# ATMEGA.net
KiCad netlist of a schematic drawn in Altium Designer
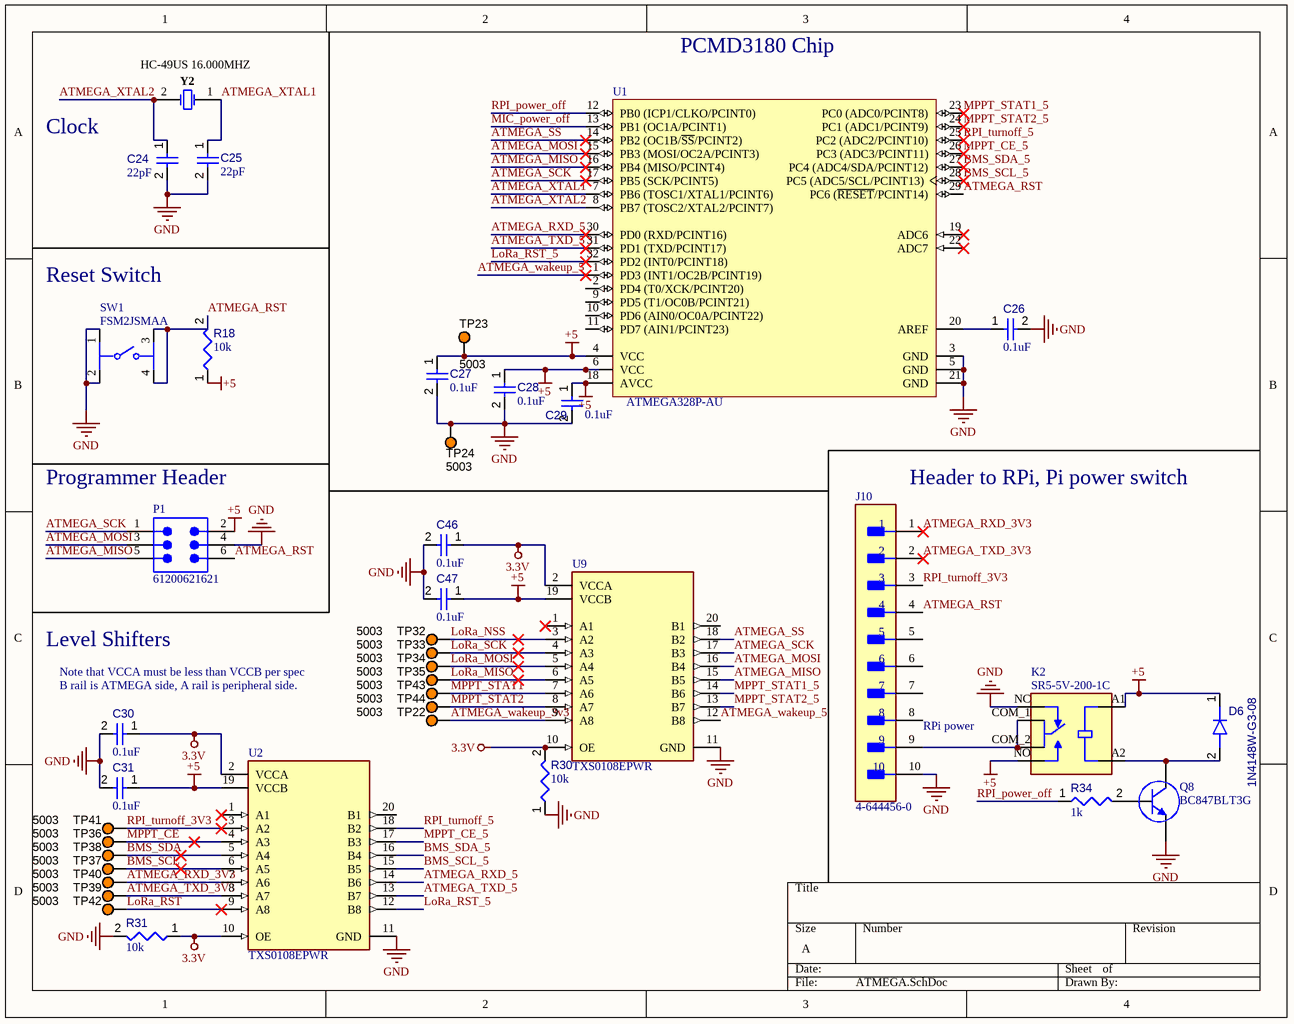
[diagram p0: ATMEGA.SchDoc]

(export (version "E")
  (design (tool "Eeschema 10.0.6"))
  (components
    (comp (ref "C24")
      (value "22pF")
      (footprint "FP-C0603C-CF-IPC_B")
      (fields (field (name "Comment") "C0603C220J5GACTU"))
      (libsource (lib "University of Michigan") (part "CAP-NP-2"))
    )
    (comp (ref "C25")
      (value "22pF")
      (footprint "FP-C0603C-CF-IPC_B")
      (fields (field (name "Comment") "C0603C220J5GACTU"))
      (libsource (lib "University of Michigan") (part "CAP-NP-2"))
    )
    (comp (ref "C26")
      (value "0.1uF")
      (footprint "CAPC1608X90X40NL10T20")
      (description "Chip Capacitor, 100 nF, +/- 10%, 50 V, 0603 (1608 Metric)")
      (fields (field (name "TOLERANCE") "10%") (field (name "Comment") "Capacitor 100 nF +/-10% 50 V 0603"))
      (libsource (lib "University of Michigan") (part "CAP-NP-2"))
    )
    (comp (ref "C27")
      (value "0.1uF")
      (footprint "CAPC1608X90X40NL10T20")
      (description "Chip Capacitor, 100 nF, +/- 10%, 50 V, 0603 (1608 Metric)")
      (fields (field (name "TOLERANCE") "10%") (field (name "Comment") "Capacitor 100 nF +/-10% 50 V 0603"))
      (libsource (lib "University of Michigan") (part "CAP-NP-2"))
    )
    (comp (ref "C28")
      (value "0.1uF")
      (footprint "CAPC1608X90X40NL10T20")
      (description "Chip Capacitor, 100 nF, +/- 10%, 50 V, 0603 (1608 Metric)")
      (fields (field (name "TOLERANCE") "10%") (field (name "Comment") "Capacitor 100 nF +/-10% 50 V 0603"))
      (libsource (lib "University of Michigan") (part "CAP-NP-2"))
    )
    (comp (ref "C29")
      (value "0.1uF")
      (footprint "CAPC1608X90X40NL10T20")
      (description "Chip Capacitor, 100 nF, +/- 10%, 50 V, 0603 (1608 Metric)")
      (fields (field (name "TOLERANCE") "10%") (field (name "Comment") "Capacitor 100 nF +/-10% 50 V 0603"))
      (libsource (lib "University of Michigan") (part "CAP-NP-2"))
    )
    (comp (ref "C30")
      (value "0.1uF")
      (footprint "CAPC1608X90X40NL10T20")
      (description "Chip Capacitor, 100 nF, +/- 10%, 50 V, 0603 (1608 Metric)")
      (fields (field (name "TOLERANCE") "10%") (field (name "Comment") "Capacitor 100 nF +/-10% 50 V 0603"))
      (libsource (lib "University of Michigan") (part "CAP-NP-2"))
    )
    (comp (ref "C31")
      (value "0.1uF")
      (footprint "CAPC1608X90X40NL10T20")
      (description "Chip Capacitor, 100 nF, +/- 10%, 50 V, 0603 (1608 Metric)")
      (fields (field (name "TOLERANCE") "10%") (field (name "Comment") "Capacitor 100 nF +/-10% 50 V 0603"))
      (libsource (lib "University of Michigan") (part "CAP-NP-2"))
    )
    (comp (ref "C46")
      (value "0.1uF")
      (footprint "CAPC1608X90X40NL10T20")
      (description "Chip Capacitor, 100 nF, +/- 10%, 50 V, 0603 (1608 Metric)")
      (fields (field (name "TOLERANCE") "10%") (field (name "Comment") "Capacitor 100 nF +/-10% 50 V 0603"))
      (libsource (lib "University of Michigan") (part "CAP-NP-2"))
    )
    (comp (ref "C47")
      (value "0.1uF")
      (footprint "CAPC1608X90X40NL10T20")
      (description "Chip Capacitor, 100 nF, +/- 10%, 50 V, 0603 (1608 Metric)")
      (fields (field (name "TOLERANCE") "10%") (field (name "Comment") "Capacitor 100 nF +/-10% 50 V 0603"))
      (libsource (lib "University of Michigan") (part "CAP-NP-2"))
    )
    (comp (ref "D6")
      (value "1N4148W-G3-08")
      (footprint "FP-S8-V-3910_01-001-IPC_B")
      (description "Rectifier Diode, 1 Phase, 1 Element, 0.15A, 100V V(RRM), Silicon")
      (libsource (lib "University of Michigan") (part "DIODE-2"))
    )
    (comp (ref "J10")
      (value "4-644456-0")
      (footprint "FP-4-644456-0-MFG")
      (libsource (lib "University of Michigan") (part "aee40dc8b284c03a16094555aa210be"))
    )
    (comp (ref "K2")
      (value "SR5-5V-200-1C")
      (footprint "RELAY_SR5-5V-200-1C")
      (description "15.6 x 10.6 x 11.8 mm, 5 V, 1 A, SPDT (1 Form C), Through Hole, Signal Relay")
      (fields (field (name "MF") "CUI Devices"))
      (libsource (lib "University of Michigan") (part "SR5-5V-200-1C"))
    )
    (comp (ref "P1")
      (value "61200621621")
      (footprint "61200621621")
      (description "Board Connector, 6 Contact(s), 2 Row(s), Male, Straight, Solder Terminal")
      (libsource (lib "University of Michigan") (part "Header_Male_2R_06P"))
    )
    (comp (ref "Q8")
      (value "BC847BLT3G")
      (footprint "ONSC-SOT-23-3-318-08_V")
      (description "Small Signal Bipolar Transistor, 0.1A I(C), 45V V(BR)CEO, 1-Element, NPN, Silicon, TO-236")
      (libsource (lib "University of Michigan") (part "TRANS-NPN-3"))
    )
    (comp (ref "R18")
      (value "10k")
      (footprint "RESC0603(1608)_L")
      (description "Chip Resistor, 120 Ohms, +/-5 %, 0.1 W, -55 to 155 degC, 0603")
      (fields (field (name "POWER") "100mW") (field (name "TOLERANCE") "5%"))
      (libsource (lib "University of Michigan") (part "RES-2"))
    )
    (comp (ref "R30")
      (value "10k")
      (footprint "RESC0603(1608)_L")
      (description "Chip Resistor, 120 Ohms, +/-5 %, 0.1 W, -55 to 155 degC, 0603")
      (fields (field (name "POWER") "100mW") (field (name "TOLERANCE") "5%"))
      (libsource (lib "University of Michigan") (part "RES-2"))
    )
    (comp (ref "R31")
      (value "10k")
      (footprint "RESC0603(1608)_L")
      (description "Chip Resistor, 120 Ohms, +/-5 %, 0.1 W, -55 to 155 degC, 0603")
      (fields (field (name "POWER") "100mW") (field (name "TOLERANCE") "5%"))
      (libsource (lib "University of Michigan") (part "RES-2"))
    )
    (comp (ref "R34")
      (value "1k")
      (footprint "RESC0603(1608)_L")
      (description "Chip Resistor, 120 Ohms, +/-5 %, 0.1 W, -55 to 155 degC, 0603")
      (fields (field (name "POWER") "100mW") (field (name "TOLERANCE") "5%"))
      (libsource (lib "University of Michigan") (part "RES-2"))
    )
    (comp (ref "SW1")
      (value "FSM2JSMAA")
      (footprint "FP-FSM2JSMAA-MFG")
      (libsource (lib "University of Michigan") (part "b8895f3f4cefb76e1819d2863dba89b"))
    )
    (comp (ref "TP22")
      (value "5003")
      (footprint "KSTN-5003")
      (description "Test Point, Orange, Height 4.6 mm, Tail Length 3 mm, 1-Pin THD, RoHS")
      (fields (field (name "MANUFACTURER") "Keystone"))
      (libsource (lib "University of Michigan") (part "TESTPOINT_ORANGE"))
    )
    (comp (ref "TP23")
      (value "5003")
      (footprint "KSTN-5003")
      (description "Test Point, Orange, Height 4.6 mm, Tail Length 3 mm, 1-Pin THD, RoHS")
      (fields (field (name "MANUFACTURER") "Keystone"))
      (libsource (lib "University of Michigan") (part "TESTPOINT_ORANGE"))
    )
    (comp (ref "TP24")
      (value "5003")
      (footprint "KSTN-5003")
      (description "Test Point, Orange, Height 4.6 mm, Tail Length 3 mm, 1-Pin THD, RoHS")
      (fields (field (name "MANUFACTURER") "Keystone"))
      (libsource (lib "University of Michigan") (part "TESTPOINT_ORANGE"))
    )
    (comp (ref "TP32")
      (value "5003")
      (footprint "KSTN-5003")
      (description "Test Point, Orange, Height 4.6 mm, Tail Length 3 mm, 1-Pin THD, RoHS")
      (fields (field (name "MANUFACTURER") "Keystone"))
      (libsource (lib "University of Michigan") (part "TESTPOINT_ORANGE"))
    )
    (comp (ref "TP33")
      (value "5003")
      (footprint "KSTN-5003")
      (description "Test Point, Orange, Height 4.6 mm, Tail Length 3 mm, 1-Pin THD, RoHS")
      (fields (field (name "MANUFACTURER") "Keystone"))
      (libsource (lib "University of Michigan") (part "TESTPOINT_ORANGE"))
    )
    (comp (ref "TP34")
      (value "5003")
      (footprint "KSTN-5003")
      (description "Test Point, Orange, Height 4.6 mm, Tail Length 3 mm, 1-Pin THD, RoHS")
      (fields (field (name "MANUFACTURER") "Keystone"))
      (libsource (lib "University of Michigan") (part "TESTPOINT_ORANGE"))
    )
    (comp (ref "TP35")
      (value "5003")
      (footprint "KSTN-5003")
      (description "Test Point, Orange, Height 4.6 mm, Tail Length 3 mm, 1-Pin THD, RoHS")
      (fields (field (name "MANUFACTURER") "Keystone"))
      (libsource (lib "University of Michigan") (part "TESTPOINT_ORANGE"))
    )
    (comp (ref "TP36")
      (value "5003")
      (footprint "KSTN-5003")
      (description "Test Point, Orange, Height 4.6 mm, Tail Length 3 mm, 1-Pin THD, RoHS")
      (fields (field (name "MANUFACTURER") "Keystone"))
      (libsource (lib "University of Michigan") (part "TESTPOINT_ORANGE"))
    )
    (comp (ref "TP37")
      (value "5003")
      (footprint "KSTN-5003")
      (description "Test Point, Orange, Height 4.6 mm, Tail Length 3 mm, 1-Pin THD, RoHS")
      (fields (field (name "MANUFACTURER") "Keystone"))
      (libsource (lib "University of Michigan") (part "TESTPOINT_ORANGE"))
    )
    (comp (ref "TP38")
      (value "5003")
      (footprint "KSTN-5003")
      (description "Test Point, Orange, Height 4.6 mm, Tail Length 3 mm, 1-Pin THD, RoHS")
      (fields (field (name "MANUFACTURER") "Keystone"))
      (libsource (lib "University of Michigan") (part "TESTPOINT_ORANGE"))
    )
    (comp (ref "TP39")
      (value "5003")
      (footprint "KSTN-5003")
      (description "Test Point, Orange, Height 4.6 mm, Tail Length 3 mm, 1-Pin THD, RoHS")
      (fields (field (name "MANUFACTURER") "Keystone"))
      (libsource (lib "University of Michigan") (part "TESTPOINT_ORANGE"))
    )
    (comp (ref "TP40")
      (value "5003")
      (footprint "KSTN-5003")
      (description "Test Point, Orange, Height 4.6 mm, Tail Length 3 mm, 1-Pin THD, RoHS")
      (fields (field (name "MANUFACTURER") "Keystone"))
      (libsource (lib "University of Michigan") (part "TESTPOINT_ORANGE"))
    )
    (comp (ref "TP41")
      (value "5003")
      (footprint "KSTN-5003")
      (description "Test Point, Orange, Height 4.6 mm, Tail Length 3 mm, 1-Pin THD, RoHS")
      (fields (field (name "MANUFACTURER") "Keystone"))
      (libsource (lib "University of Michigan") (part "TESTPOINT_ORANGE"))
    )
    (comp (ref "TP42")
      (value "5003")
      (footprint "KSTN-5003")
      (description "Test Point, Orange, Height 4.6 mm, Tail Length 3 mm, 1-Pin THD, RoHS")
      (fields (field (name "MANUFACTURER") "Keystone"))
      (libsource (lib "University of Michigan") (part "TESTPOINT_ORANGE"))
    )
    (comp (ref "TP43")
      (value "5003")
      (footprint "KSTN-5003")
      (description "Test Point, Orange, Height 4.6 mm, Tail Length 3 mm, 1-Pin THD, RoHS")
      (fields (field (name "MANUFACTURER") "Keystone"))
      (libsource (lib "University of Michigan") (part "TESTPOINT_ORANGE"))
    )
    (comp (ref "TP44")
      (value "5003")
      (footprint "KSTN-5003")
      (description "Test Point, Orange, Height 4.6 mm, Tail Length 3 mm, 1-Pin THD, RoHS")
      (fields (field (name "MANUFACTURER") "Keystone"))
      (libsource (lib "University of Michigan") (part "TESTPOINT_ORANGE"))
    )
    (comp (ref "U1")
      (value "ATMEGA328P-AU")
      (footprint "ATML-32A_M")
      (fields (field (name "MANUFACTURER") "Atmel"))
      (libsource (lib "University of Michigan") (part "ATML-ATMEGAX8A-32A"))
    )
    (comp (ref "U2")
      (value "TXS0108EPWR")
      (footprint "FP-PW0020A-IPC_A")
      (description "Interface Circuit, PDSO20")
      (libsource (lib "University of Michigan") (part "86128ddf5852d4e934b2dd0188c13f1"))
    )
    (comp (ref "U9")
      (value "TXS0108EPWR")
      (footprint "FP-PW0020A-IPC_A")
      (description "Interface Circuit, PDSO20")
      (libsource (lib "University of Michigan") (part "86128ddf5852d4e934b2dd0188c13f1"))
    )
    (comp (ref "Y2")
      (value "HC-49US 16.000MHZ")
      (footprint "JPY-HC-49US")
      (description "Crystal, 16 MHz, +/- 30 ppm, 18 pF, -20 to 70 degC, 2-Pin THD")
      (fields (field (name "MANUFACTURER") "Jing peng yuan"))
      (libsource (lib "University of Michigan") (part "XTAL-1-2-2"))
    )
  )
  (nets
    (net (code "1") (name "+5") (class "Default")
      (node (ref "C27") (pin "1") (pinfunction "1_1") (pintype "passive"))
      (node (ref "C28") (pin "1") (pinfunction "1_1") (pintype "passive"))
      (node (ref "C29") (pin "1") (pinfunction "1_1") (pintype "passive"))
      (node (ref "C31") (pin "1") (pinfunction "1_1") (pintype "passive"))
      (node (ref "C47") (pin "1") (pinfunction "1_1") (pintype "passive"))
      (node (ref "D6") (pin "1") (pinfunction "K_1") (pintype "passive"))
      (node (ref "K2") (pin "A1") (pinfunction "COIL1_A1") (pintype "passive"))
      (node (ref "K2") (pin "NO") (pinfunction "NO_NO") (pintype "passive"))
      (node (ref "P1") (pin "2") (pinfunction "2_2") (pintype "passive"))
      (node (ref "R18") (pin "1") (pinfunction "1_1") (pintype "passive"))
      (node (ref "TP23") (pin "1") (pinfunction "1_1") (pintype "passive"))
      (node (ref "U1") (pin "18") (pinfunction "AVCC_18") (pintype "power_in"))
      (node (ref "U1") (pin "4") (pinfunction "VCC_4") (pintype "power_in"))
      (node (ref "U1") (pin "6") (pinfunction "VCC_6") (pintype "power_in"))
      (node (ref "U2") (pin "19") (pinfunction "VCCB_19") (pintype "power_in"))
      (node (ref "U9") (pin "19") (pinfunction "VCCB_19") (pintype "power_in"))
    )
    (net (code "2") (name "/ATMEGA_MISO") (class "Default")
      (node (ref "P1") (pin "5") (pinfunction "5_5") (pintype "passive"))
      (node (ref "U1") (pin "16") (pinfunction "PB4_(MISO/PCINT4)_16") (pintype "bidirectional"))
      (node (ref "U9") (pin "15") (pinfunction "B5_15") (pintype "output"))
    )
    (net (code "3") (name "/ATMEGA_MOSI") (class "Default")
      (node (ref "P1") (pin "3") (pinfunction "3_3") (pintype "passive"))
      (node (ref "U1") (pin "15") (pinfunction "PB3_(MOSI/OC2A/PCINT3)_15") (pintype "bidirectional"))
      (node (ref "U9") (pin "16") (pinfunction "B4_16") (pintype "output"))
    )
    (net (code "4") (name "/ATMEGA_RST") (class "Default")
      (node (ref "J10") (pin "4") (pinfunction "4_4") (pintype "passive"))
      (node (ref "P1") (pin "6") (pinfunction "6_6") (pintype "passive"))
      (node (ref "R18") (pin "2") (pinfunction "2_2") (pintype "passive"))
      (node (ref "SW1") (pin "3") (pinfunction "3_3") (pintype "passive"))
      (node (ref "SW1") (pin "4") (pinfunction "4_4") (pintype "passive"))
      (node (ref "U1") (pin "29") (pinfunction "PC6_(~{RESET}/PCINT14)_29") (pintype "bidirectional"))
    )
    (net (code "5") (name "/ATMEGA_RXD_3V3") (class "Default")
      (node (ref "J10") (pin "1") (pinfunction "1_1") (pintype "passive"))
      (node (ref "TP40") (pin "1") (pinfunction "1_1") (pintype "passive"))
      (node (ref "U2") (pin "7") (pinfunction "A6_7") (pintype "input"))
    )
    (net (code "6") (name "/ATMEGA_RXD_5") (class "Default")
      (node (ref "U1") (pin "30") (pinfunction "PD0_(RXD/PCINT16)_30") (pintype "bidirectional"))
      (node (ref "U2") (pin "14") (pinfunction "B6_14") (pintype "output"))
    )
    (net (code "7") (name "/ATMEGA_SCK") (class "Default")
      (node (ref "P1") (pin "1") (pinfunction "1_1") (pintype "passive"))
      (node (ref "U1") (pin "17") (pinfunction "PB5_(SCK/PCINT5)_17") (pintype "bidirectional"))
      (node (ref "U9") (pin "17") (pinfunction "B3_17") (pintype "output"))
    )
    (net (code "8") (name "/ATMEGA_SS") (class "Default")
      (node (ref "U1") (pin "14") (pinfunction "PB2_(OC1B/~{SS}/PCINT2)_14") (pintype "bidirectional"))
      (node (ref "U9") (pin "18") (pinfunction "B2_18") (pintype "output"))
    )
    (net (code "9") (name "/ATMEGA_TXD_3V3") (class "Default")
      (node (ref "J10") (pin "2") (pinfunction "2_2") (pintype "passive"))
      (node (ref "TP39") (pin "1") (pinfunction "1_1") (pintype "passive"))
      (node (ref "U2") (pin "8") (pinfunction "A7_8") (pintype "input"))
    )
    (net (code "10") (name "/ATMEGA_TXD_5") (class "Default")
      (node (ref "U1") (pin "31") (pinfunction "PD1_(TXD/PCINT17)_31") (pintype "bidirectional"))
      (node (ref "U2") (pin "13") (pinfunction "B7_13") (pintype "output"))
    )
    (net (code "11") (name "/ATMEGA_XTAL1") (class "Default")
      (node (ref "C25") (pin "1") (pinfunction "1_1") (pintype "passive"))
      (node (ref "U1") (pin "7") (pinfunction "PB6_(TOSC1/XTAL1/PCINT6)_7") (pintype "bidirectional"))
      (node (ref "Y2") (pin "1") (pinfunction "1_1") (pintype "passive"))
    )
    (net (code "12") (name "/ATMEGA_XTAL2") (class "Default")
      (node (ref "C24") (pin "1") (pinfunction "1_1") (pintype "passive"))
      (node (ref "U1") (pin "8") (pinfunction "PB7_(TOSC2/XTAL2/PCINT7)_8") (pintype "bidirectional"))
      (node (ref "Y2") (pin "2") (pinfunction "2_2") (pintype "passive"))
    )
    (net (code "13") (name "/ATMEGA_wakeup_3v3") (class "Default")
      (node (ref "TP22") (pin "1") (pinfunction "1_1") (pintype "passive"))
      (node (ref "U9") (pin "9") (pinfunction "A8_9") (pintype "input"))
    )
    (net (code "14") (name "/ATMEGA_wakeup_5") (class "Default")
      (node (ref "U1") (pin "1") (pinfunction "PD3_(INT1/OC2B/PCINT19)_1") (pintype "bidirectional"))
      (node (ref "U9") (pin "12") (pinfunction "B8_12") (pintype "output"))
    )
    (net (code "15") (name "/BMS_SCL") (class "Default")
      (node (ref "TP37") (pin "1") (pinfunction "1_1") (pintype "passive"))
      (node (ref "U2") (pin "6") (pinfunction "A5_6") (pintype "input"))
    )
    (net (code "16") (name "/BMS_SCL_5") (class "Default")
      (node (ref "U1") (pin "28") (pinfunction "PC5_(ADC5/SCL/PCINT13)_28") (pintype "bidirectional"))
      (node (ref "U2") (pin "15") (pinfunction "B5_15") (pintype "output"))
    )
    (net (code "17") (name "/BMS_SDA") (class "Default")
      (node (ref "TP38") (pin "1") (pinfunction "1_1") (pintype "passive"))
      (node (ref "U2") (pin "5") (pinfunction "A4_5") (pintype "input"))
    )
    (net (code "18") (name "/BMS_SDA_5") (class "Default")
      (node (ref "U1") (pin "27") (pinfunction "PC4_(ADC4/SDA/PCINT12)_27") (pintype "bidirectional"))
      (node (ref "U2") (pin "16") (pinfunction "B4_16") (pintype "output"))
    )
    (net (code "19") (name "/LoRa_MISO") (class "Default")
      (node (ref "TP35") (pin "1") (pinfunction "1_1") (pintype "passive"))
      (node (ref "U9") (pin "6") (pinfunction "A5_6") (pintype "input"))
    )
    (net (code "20") (name "/LoRa_MOSI") (class "Default")
      (node (ref "TP34") (pin "1") (pinfunction "1_1") (pintype "passive"))
      (node (ref "U9") (pin "5") (pinfunction "A4_5") (pintype "input"))
    )
    (net (code "21") (name "/LoRa_NSS") (class "Default")
      (node (ref "TP32") (pin "1") (pinfunction "1_1") (pintype "passive"))
      (node (ref "U9") (pin "3") (pinfunction "A2_3") (pintype "input"))
    )
    (net (code "22") (name "/LoRa_RST") (class "Default")
      (node (ref "TP42") (pin "1") (pinfunction "1_1") (pintype "passive"))
      (node (ref "U2") (pin "9") (pinfunction "A8_9") (pintype "input"))
    )
    (net (code "23") (name "/LoRa_RST_5") (class "Default")
      (node (ref "U1") (pin "32") (pinfunction "PD2_(INT0/PCINT18)_32") (pintype "bidirectional"))
      (node (ref "U2") (pin "12") (pinfunction "B8_12") (pintype "output"))
    )
    (net (code "24") (name "/LoRa_SCK") (class "Default")
      (node (ref "TP33") (pin "1") (pinfunction "1_1") (pintype "passive"))
      (node (ref "U9") (pin "4") (pinfunction "A3_4") (pintype "input"))
    )
    (net (code "25") (name "/MIC_power_off") (class "Default")
      (node (ref "U1") (pin "13") (pinfunction "PB1_(OC1A/PCINT1)_13") (pintype "bidirectional"))
    )
    (net (code "26") (name "/MPPT_CE") (class "Default")
      (node (ref "TP36") (pin "1") (pinfunction "1_1") (pintype "passive"))
      (node (ref "U2") (pin "4") (pinfunction "A3_4") (pintype "input"))
    )
    (net (code "27") (name "/MPPT_CE_5") (class "Default")
      (node (ref "U1") (pin "26") (pinfunction "PC3_(ADC3/PCINT11)_26") (pintype "bidirectional"))
      (node (ref "U2") (pin "17") (pinfunction "B3_17") (pintype "output"))
    )
    (net (code "28") (name "/MPPT_STAT1") (class "Default")
      (node (ref "TP43") (pin "1") (pinfunction "1_1") (pintype "passive"))
      (node (ref "U9") (pin "7") (pinfunction "A6_7") (pintype "input"))
    )
    (net (code "29") (name "/MPPT_STAT1_5") (class "Default")
      (node (ref "U1") (pin "23") (pinfunction "PC0_(ADC0/PCINT8)_23") (pintype "bidirectional"))
      (node (ref "U9") (pin "14") (pinfunction "B6_14") (pintype "output"))
    )
    (net (code "30") (name "/MPPT_STAT2") (class "Default")
      (node (ref "TP44") (pin "1") (pinfunction "1_1") (pintype "passive"))
      (node (ref "U9") (pin "8") (pinfunction "A7_8") (pintype "input"))
    )
    (net (code "31") (name "/MPPT_STAT2_5") (class "Default")
      (node (ref "U1") (pin "24") (pinfunction "PC1_(ADC1/PCINT9)_24") (pintype "bidirectional"))
      (node (ref "U9") (pin "13") (pinfunction "B7_13") (pintype "output"))
    )
    (net (code "32") (name "/RPI_power_off") (class "Default")
      (node (ref "R34") (pin "1") (pinfunction "1_1") (pintype "passive"))
      (node (ref "U1") (pin "12") (pinfunction "PB0_(ICP1/CLKO/PCINT0)_12") (pintype "bidirectional"))
    )
    (net (code "33") (name "/RPI_turnoff_3V3") (class "Default")
      (node (ref "J10") (pin "3") (pinfunction "3_3") (pintype "passive"))
      (node (ref "TP41") (pin "1") (pinfunction "1_1") (pintype "passive"))
      (node (ref "U2") (pin "3") (pinfunction "A2_3") (pintype "input"))
    )
    (net (code "34") (name "/RPI_turnoff_5") (class "Default")
      (node (ref "U1") (pin "25") (pinfunction "PC2_(ADC2/PCINT10)_25") (pintype "bidirectional"))
      (node (ref "U2") (pin "18") (pinfunction "B2_18") (pintype "output"))
    )
    (net (code "35") (name "3.3V") (class "Default")
      (node (ref "C30") (pin "1") (pinfunction "1_1") (pintype "passive"))
      (node (ref "C46") (pin "1") (pinfunction "1_1") (pintype "passive"))
      (node (ref "R30") (pin "2") (pinfunction "2_2") (pintype "passive"))
      (node (ref "R31") (pin "1") (pinfunction "1_1") (pintype "passive"))
      (node (ref "U2") (pin "10") (pinfunction "OE_10") (pintype "input"))
      (node (ref "U2") (pin "2") (pinfunction "VCCA_2") (pintype "power_in"))
      (node (ref "U9") (pin "10") (pinfunction "OE_10") (pintype "input"))
      (node (ref "U9") (pin "2") (pinfunction "VCCA_2") (pintype "power_in"))
    )
    (net (code "36") (name "GND") (class "Default")
      (node (ref "C24") (pin "2") (pinfunction "2_2") (pintype "passive"))
      (node (ref "C25") (pin "2") (pinfunction "2_2") (pintype "passive"))
      (node (ref "C26") (pin "2") (pinfunction "2_2") (pintype "passive"))
      (node (ref "C27") (pin "2") (pinfunction "2_2") (pintype "passive"))
      (node (ref "C28") (pin "2") (pinfunction "2_2") (pintype "passive"))
      (node (ref "C29") (pin "2") (pinfunction "2_2") (pintype "passive"))
      (node (ref "C30") (pin "2") (pinfunction "2_2") (pintype "passive"))
      (node (ref "C31") (pin "2") (pinfunction "2_2") (pintype "passive"))
      (node (ref "C46") (pin "2") (pinfunction "2_2") (pintype "passive"))
      (node (ref "C47") (pin "2") (pinfunction "2_2") (pintype "passive"))
      (node (ref "J10") (pin "10") (pinfunction "10_10") (pintype "passive"))
      (node (ref "K2") (pin "NC") (pinfunction "NC_NC") (pintype "passive"))
      (node (ref "P1") (pin "4") (pinfunction "4_4") (pintype "passive"))
      (node (ref "Q8") (pin "1") (pinfunction "E_1") (pintype "passive"))
      (node (ref "R30") (pin "1") (pinfunction "1_1") (pintype "passive"))
      (node (ref "R31") (pin "2") (pinfunction "2_2") (pintype "passive"))
      (node (ref "SW1") (pin "1") (pinfunction "1_1") (pintype "passive"))
      (node (ref "SW1") (pin "2") (pinfunction "2_2") (pintype "passive"))
      (node (ref "TP24") (pin "1") (pinfunction "1_1") (pintype "passive"))
      (node (ref "U1") (pin "21") (pinfunction "GND_21") (pintype "power_in"))
      (node (ref "U1") (pin "3") (pinfunction "GND_3") (pintype "power_in"))
      (node (ref "U1") (pin "5") (pinfunction "GND_5") (pintype "power_in"))
      (node (ref "U2") (pin "11") (pinfunction "GND_11") (pintype "power_in"))
      (node (ref "U9") (pin "11") (pinfunction "GND_11") (pintype "power_in"))
    )
    (net (code "37") (name "Net-(D6-A)") (class "Default")
      (node (ref "D6") (pin "2") (pinfunction "A_2") (pintype "passive"))
      (node (ref "K2") (pin "A2") (pinfunction "COIL2_A2") (pintype "passive"))
      (node (ref "Q8") (pin "3") (pinfunction "C_3") (pintype "passive"))
    )
    (net (code "38") (name "Net-(K2-COM1)") (class "Default")
      (node (ref "J10") (pin "9") (pinfunction "9_9") (pintype "passive"))
      (node (ref "K2") (pin "COM_1") (pinfunction "COM1_COM_1") (pintype "passive"))
      (node (ref "K2") (pin "COM_2") (pinfunction "COM2_COM_2") (pintype "passive"))
    )
    (net (code "39") (name "Net-(Q8-B)") (class "Default")
      (node (ref "Q8") (pin "2") (pinfunction "B_2") (pintype "passive"))
      (node (ref "R34") (pin "2") (pinfunction "2_2") (pintype "passive"))
    )
    (net (code "40") (name "Net-(U1-AREF)") (class "Default")
      (node (ref "C26") (pin "1") (pinfunction "1_1") (pintype "passive"))
      (node (ref "U1") (pin "20") (pinfunction "AREF_20") (pintype "passive"))
    )
    (net (code "41") (name "unconnected-(J10-Pad5)") (class "Default")
      (node (ref "J10") (pin "5") (pinfunction "5_5") (pintype "passive"))
    )
    (net (code "42") (name "unconnected-(J10-Pad6)") (class "Default")
      (node (ref "J10") (pin "6") (pinfunction "6_6") (pintype "passive"))
    )
    (net (code "43") (name "unconnected-(J10-Pad7)") (class "Default")
      (node (ref "J10") (pin "7") (pinfunction "7_7") (pintype "passive"))
    )
    (net (code "44") (name "unconnected-(J10-Pad8)") (class "Default")
      (node (ref "J10") (pin "8") (pinfunction "8_8") (pintype "passive"))
    )
    (net (code "45") (name "unconnected-(U1-ADC6-Pad19)") (class "Default")
      (node (ref "U1") (pin "19") (pinfunction "ADC6_19") (pintype "input+no_connect"))
    )
    (net (code "46") (name "unconnected-(U1-ADC7-Pad22)") (class "Default")
      (node (ref "U1") (pin "22") (pinfunction "ADC7_22") (pintype "input+no_connect"))
    )
    (net (code "47") (name "unconnected-(U1-PD4_(T0{slash}XCK{slash}PCINT20)-Pad2)") (class "Default")
      (node (ref "U1") (pin "2") (pinfunction "PD4_(T0/XCK/PCINT20)_2") (pintype "bidirectional"))
    )
    (net (code "48") (name "unconnected-(U1-PD5_(T1{slash}OC0B{slash}PCINT21)-Pad9)") (class "Default")
      (node (ref "U1") (pin "9") (pinfunction "PD5_(T1/OC0B/PCINT21)_9") (pintype "bidirectional"))
    )
    (net (code "49") (name "unconnected-(U1-PD6_(AIN0{slash}OC0A{slash}PCINT22)-Pad10)") (class "Default")
      (node (ref "U1") (pin "10") (pinfunction "PD6_(AIN0/OC0A/PCINT22)_10") (pintype "bidirectional"))
    )
    (net (code "50") (name "unconnected-(U1-PD7_(AIN1{slash}PCINT23)-Pad11)") (class "Default")
      (node (ref "U1") (pin "11") (pinfunction "PD7_(AIN1/PCINT23)_11") (pintype "bidirectional"))
    )
    (net (code "51") (name "unconnected-(U2-A1-Pad1)") (class "Default")
      (node (ref "U2") (pin "1") (pinfunction "A1_1") (pintype "input+no_connect"))
    )
    (net (code "52") (name "unconnected-(U2-B1-Pad20)") (class "Default")
      (node (ref "U2") (pin "20") (pinfunction "B1_20") (pintype "output"))
    )
    (net (code "53") (name "unconnected-(U9-A1-Pad1)") (class "Default")
      (node (ref "U9") (pin "1") (pinfunction "A1_1") (pintype "input+no_connect"))
    )
    (net (code "54") (name "unconnected-(U9-B1-Pad20)") (class "Default")
      (node (ref "U9") (pin "20") (pinfunction "B1_20") (pintype "output"))
    )
  )
)
